# ProgShield.net
KiCad netlist of a schematic drawn in EAGLE
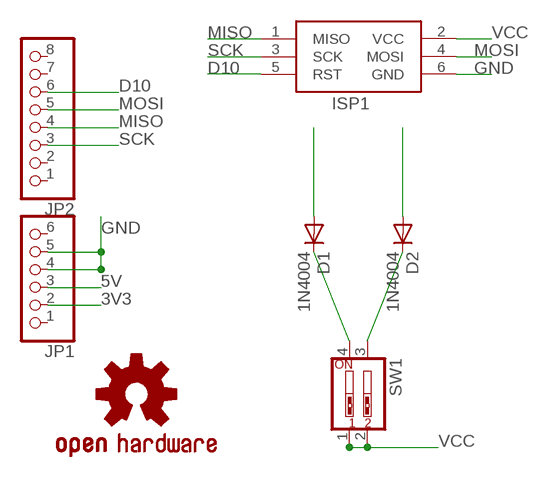
[diagram p0: schematic, sheet 1]

(export (version "E")
  (design (tool "Eeschema 10.0.6"))
  (components
    (comp (ref "D1")
      (value "1N4004")
      (footprint "eagle-import:DO41-10")
      (libsource (lib "eagle-import") (part "1N4004"))
    )
    (comp (ref "D2")
      (value "1N4004")
      (footprint "eagle-import:DO41-10")
      (libsource (lib "eagle-import") (part "1N4004"))
    )
    (comp (ref "ISP1")
      (value "AVRISP-6")
      (footprint "eagle-import:AVRISP")
      (libsource (lib "eagle-import") (part "AVRISP-6"))
    )
    (comp (ref "JP1")
      (value "PINHD-1X6CB")
      (footprint "eagle-import:1X06-CLEANBIG")
      (libsource (lib "eagle-import") (part "PINHD-1X6CB"))
    )
    (comp (ref "JP2")
      (value "PINHD-1X8CLEANBIG")
      (footprint "eagle-import:1X08-CLEANBIG")
      (libsource (lib "eagle-import") (part "PINHD-1X8CLEANBIG"))
    )
    (comp (ref "SW1")
      (value "SW_DIP-2")
      (footprint "eagle-import:EDG-02")
      (libsource (lib "eagle-import") (part "SW_DIP-2"))
    )
    (comp (ref "U$1")
      (value "OSHW-LOGOL")
      (footprint "eagle-import:OSHW-LOGO-L")
      (libsource (lib "eagle-import") (part "OSHW-LOGOL"))
    )
  )
  (nets
    (net (code "1") (name "/3V3") (class "Default")
      (node (ref "D2") (pin "A") (pinfunction "A_A") (pintype "passive"))
      (node (ref "JP1") (pin "2") (pinfunction "2_2") (pintype "passive"))
    )
    (net (code "2") (name "/5V") (class "Default")
      (node (ref "D1") (pin "A") (pinfunction "A_A") (pintype "passive"))
      (node (ref "JP1") (pin "3") (pinfunction "3_3") (pintype "passive"))
    )
    (net (code "3") (name "/D10") (class "Default")
      (node (ref "ISP1") (pin "5") (pinfunction "RST_5") (pintype "output"))
      (node (ref "JP2") (pin "6") (pinfunction "6_6") (pintype "passive"))
    )
    (net (code "4") (name "/GND") (class "Default")
      (node (ref "ISP1") (pin "6") (pinfunction "GND_6") (pintype "power_in"))
      (node (ref "JP1") (pin "4") (pinfunction "4_4") (pintype "passive"))
      (node (ref "JP1") (pin "5") (pinfunction "5_5") (pintype "passive"))
    )
    (net (code "5") (name "/MISO") (class "Default")
      (node (ref "ISP1") (pin "1") (pinfunction "MISO_1") (pintype "input"))
      (node (ref "JP2") (pin "4") (pinfunction "4_4") (pintype "passive"))
    )
    (net (code "6") (name "/MOSI") (class "Default")
      (node (ref "ISP1") (pin "4") (pinfunction "MOSI_4") (pintype "output"))
      (node (ref "JP2") (pin "5") (pinfunction "5_5") (pintype "passive"))
    )
    (net (code "7") (name "/SCK") (class "Default")
      (node (ref "ISP1") (pin "3") (pinfunction "SCK_3") (pintype "output"))
      (node (ref "JP2") (pin "3") (pinfunction "3_3") (pintype "passive"))
    )
    (net (code "8") (name "/VCC") (class "Default")
      (node (ref "ISP1") (pin "2") (pinfunction "VCC_2") (pintype "power_in"))
      (node (ref "SW1") (pin "1") (pinfunction "1_1") (pintype "passive"))
      (node (ref "SW1") (pin "2") (pinfunction "2_2") (pintype "passive"))
    )
    (net (code "9") (name "Net-(D1-PadC)") (class "Default")
      (node (ref "D1") (pin "C") (pinfunction "C_C") (pintype "passive"))
      (node (ref "SW1") (pin "4") (pinfunction "4_4") (pintype "passive"))
    )
    (net (code "10") (name "Net-(D2-PadC)") (class "Default")
      (node (ref "D2") (pin "C") (pinfunction "C_C") (pintype "passive"))
      (node (ref "SW1") (pin "3") (pinfunction "3_3") (pintype "passive"))
    )
    (net (code "11") (name "unconnected-(JP1-Pad1)") (class "Default")
      (node (ref "JP1") (pin "1") (pinfunction "1_1") (pintype "passive"))
    )
    (net (code "12") (name "unconnected-(JP1-Pad6)") (class "Default")
      (node (ref "JP1") (pin "6") (pinfunction "6_6") (pintype "passive"))
    )
    (net (code "13") (name "unconnected-(JP2-Pad1)") (class "Default")
      (node (ref "JP2") (pin "1") (pinfunction "1_1") (pintype "passive"))
    )
    (net (code "14") (name "unconnected-(JP2-Pad2)") (class "Default")
      (node (ref "JP2") (pin "2") (pinfunction "2_2") (pintype "passive"))
    )
    (net (code "15") (name "unconnected-(JP2-Pad7)") (class "Default")
      (node (ref "JP2") (pin "7") (pinfunction "7_7") (pintype "passive"))
    )
    (net (code "16") (name "unconnected-(JP2-Pad8)") (class "Default")
      (node (ref "JP2") (pin "8") (pinfunction "8_8") (pintype "passive"))
    )
  )
)
